# SchemaDriverMoteur.net
KiCad netlist of a schematic drawn in Altium Designer
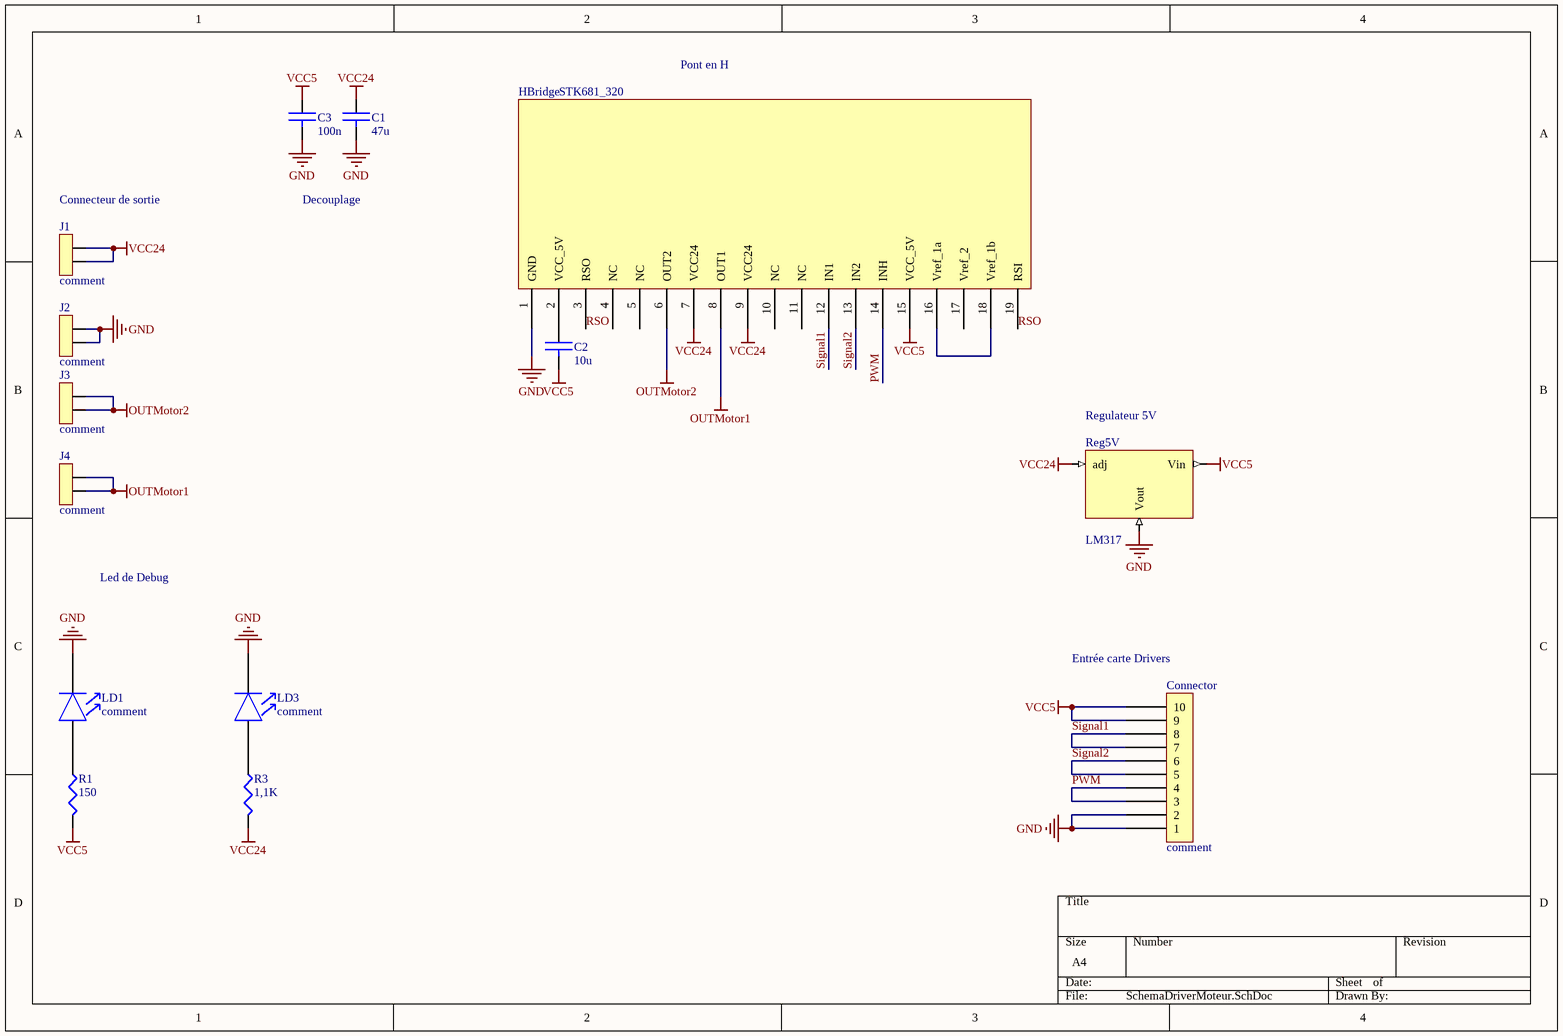
[diagram p0: SchemaDriverMoteur.SchDoc]

(export (version "E")
  (design (tool "Eeschema 10.0.6"))
  (components
    (comp (ref "C1")
      (value "47u")
      (footprint "RAD0.1")
      (description "capacité non polarisée")
      (fields (field (name "Comment") "CAP"))
      (libsource (lib "ISEN_basics") (part "CAP"))
    )
    (comp (ref "C2")
      (value "10u")
      (footprint "RAD0.1")
      (description "capacité non polarisée")
      (fields (field (name "Comment") "CAP"))
      (libsource (lib "ISEN_basics") (part "CAP"))
    )
    (comp (ref "C3")
      (value "100n")
      (footprint "0805")
      (description "capacité non polarisée")
      (fields (field (name "Comment") "CAP"))
      (libsource (lib "ISEN_basics") (part "CAP"))
    )
    (comp (ref "Connector")
      (value "comment")
      (footprint "HE10-10V")
      (description "10-pin connector")
      (libsource (lib "ISEN_basics") (part "HE10-10"))
    )
    (comp (ref "HBridge")
      (value "STK681_320")
      (footprint "stk681_320")
      (libsource (lib "STK681_320") (part "STK681_320"))
    )
    (comp (ref "J1")
      (value "comment")
      (footprint "AMP_2")
      (description "connecteur alim 2 pôles")
      (libsource (lib "ISEN_basics") (part "POWER2"))
    )
    (comp (ref "J2")
      (value "comment")
      (footprint "AMP_2")
      (description "connecteur alim 2 pôles")
      (libsource (lib "ISEN_basics") (part "POWER2"))
    )
    (comp (ref "J3")
      (value "comment")
      (footprint "AMP_2")
      (description "connecteur alim 2 pôles")
      (libsource (lib "ISEN_basics") (part "POWER2"))
    )
    (comp (ref "J4")
      (value "comment")
      (footprint "AMP_2")
      (description "connecteur alim 2 pôles")
      (libsource (lib "ISEN_basics") (part "POWER2"))
    )
    (comp (ref "LD1")
      (value "comment")
      (footprint "LED0805")
      (description "LED 5mm/3mm/CMS")
      (libsource (lib "ISEN_basics") (part "LED"))
    )
    (comp (ref "LD3")
      (value "comment")
      (footprint "LED0805")
      (description "LED 5mm/3mm/CMS")
      (libsource (lib "ISEN_basics") (part "LED"))
    )
    (comp (ref "R1")
      (value "150")
      (footprint "0805")
      (description "resistance")
      (fields (field (name "Comment") "RES"))
      (libsource (lib "ISEN_basics") (part "RES"))
    )
    (comp (ref "R3")
      (value "1,1K")
      (footprint "0805")
      (description "resistance")
      (fields (field (name "Comment") "RES"))
      (libsource (lib "ISEN_basics") (part "RES"))
    )
    (comp (ref "Reg5V")
      (value "LM317")
      (footprint "TO220V")
      (description "régulateur positif ajustable")
      (libsource (lib "ISEN_basics") (part "REG_ADJ_POS"))
    )
  )
  (nets
    (net (code "1") (name "/PWM") (class "Default")
      (node (ref "Connector") (pin "3") (pinfunction "3_3") (pintype "passive"))
      (node (ref "Connector") (pin "4") (pinfunction "4_4") (pintype "passive"))
      (node (ref "HBridge") (pin "14") (pinfunction "INH_14") (pintype "passive"))
    )
    (net (code "2") (name "/RSO") (class "Default")
      (node (ref "HBridge") (pin "19") (pinfunction "RSI_19") (pintype "passive"))
      (node (ref "HBridge") (pin "3") (pinfunction "RSO_3") (pintype "passive"))
    )
    (net (code "3") (name "/Signal1") (class "Default")
      (node (ref "Connector") (pin "7") (pinfunction "7_7") (pintype "passive"))
      (node (ref "Connector") (pin "8") (pinfunction "8_8") (pintype "passive"))
      (node (ref "HBridge") (pin "12") (pinfunction "IN1_12") (pintype "passive"))
    )
    (net (code "4") (name "/Signal2") (class "Default")
      (node (ref "Connector") (pin "5") (pinfunction "5_5") (pintype "passive"))
      (node (ref "Connector") (pin "6") (pinfunction "6_6") (pintype "passive"))
      (node (ref "HBridge") (pin "13") (pinfunction "IN2_13") (pintype "passive"))
    )
    (net (code "5") (name "GND") (class "Default")
      (node (ref "C1") (pin "2") (pinfunction "2_2") (pintype "passive"))
      (node (ref "C3") (pin "2") (pinfunction "2_2") (pintype "passive"))
      (node (ref "Connector") (pin "1") (pinfunction "1_1") (pintype "passive"))
      (node (ref "Connector") (pin "2") (pinfunction "2_2") (pintype "passive"))
      (node (ref "HBridge") (pin "1") (pinfunction "GND_1") (pintype "passive"))
      (node (ref "J2") (pin "1") (pintype "passive"))
      (node (ref "J2") (pin "2") (pintype "passive"))
      (node (ref "LD1") (pin "K") (pinfunction "10_K") (pintype "passive"))
      (node (ref "LD3") (pin "K") (pinfunction "10_K") (pintype "passive"))
      (node (ref "Reg5V") (pin "2") (pinfunction "Vout_2") (pintype "input"))
    )
    (net (code "6") (name "Net-(C2-Pad1)") (class "Default")
      (node (ref "C2") (pin "1") (pinfunction "1_1") (pintype "passive"))
      (node (ref "HBridge") (pin "2") (pinfunction "VCC_5V_2") (pintype "passive"))
    )
    (net (code "7") (name "Net-(HBridge-Vref_1a)") (class "Default")
      (node (ref "HBridge") (pin "16") (pinfunction "Vref_1a_16") (pintype "passive"))
      (node (ref "HBridge") (pin "18") (pinfunction "Vref_1b_18") (pintype "passive"))
    )
    (net (code "8") (name "Net-(LD1-8)") (class "Default")
      (node (ref "LD1") (pin "A") (pinfunction "8_A") (pintype "passive"))
      (node (ref "R1") (pin "1") (pintype "passive"))
    )
    (net (code "9") (name "Net-(LD3-8)") (class "Default")
      (node (ref "LD3") (pin "A") (pinfunction "8_A") (pintype "passive"))
      (node (ref "R3") (pin "1") (pintype "passive"))
    )
    (net (code "10") (name "OUTMotor1") (class "Default")
      (node (ref "HBridge") (pin "8") (pinfunction "OUT1_8") (pintype "passive"))
      (node (ref "J4") (pin "1") (pintype "passive"))
      (node (ref "J4") (pin "2") (pintype "passive"))
    )
    (net (code "11") (name "OUTMotor2") (class "Default")
      (node (ref "HBridge") (pin "6") (pinfunction "OUT2_6") (pintype "passive"))
      (node (ref "J3") (pin "1") (pintype "passive"))
      (node (ref "J3") (pin "2") (pintype "passive"))
    )
    (net (code "12") (name "VCC5") (class "Default")
      (node (ref "C2") (pin "2") (pinfunction "2_2") (pintype "passive"))
      (node (ref "C3") (pin "1") (pinfunction "1_1") (pintype "passive"))
      (node (ref "Connector") (pin "10") (pinfunction "10_10") (pintype "passive"))
      (node (ref "Connector") (pin "9") (pinfunction "9_9") (pintype "passive"))
      (node (ref "HBridge") (pin "15") (pinfunction "VCC_5V_15") (pintype "passive"))
      (node (ref "R1") (pin "2") (pintype "passive"))
      (node (ref "Reg5V") (pin "3") (pinfunction "Vin_3") (pintype "output"))
    )
    (net (code "13") (name "VCC24") (class "Default")
      (node (ref "C1") (pin "1") (pinfunction "1_1") (pintype "passive"))
      (node (ref "HBridge") (pin "7") (pinfunction "VCC24_7") (pintype "passive"))
      (node (ref "HBridge") (pin "9") (pinfunction "VCC24_9") (pintype "passive"))
      (node (ref "J1") (pin "1") (pintype "passive"))
      (node (ref "J1") (pin "2") (pintype "passive"))
      (node (ref "R3") (pin "2") (pintype "passive"))
      (node (ref "Reg5V") (pin "1") (pinfunction "adj_1") (pintype "input"))
    )
    (net (code "14") (name "unconnected-(HBridge-NC-Pad4)") (class "Default")
      (node (ref "HBridge") (pin "4") (pinfunction "NC_4") (pintype "passive"))
    )
    (net (code "15") (name "unconnected-(HBridge-NC-Pad5)") (class "Default")
      (node (ref "HBridge") (pin "5") (pinfunction "NC_5") (pintype "passive"))
    )
    (net (code "16") (name "unconnected-(HBridge-NC-Pad10)") (class "Default")
      (node (ref "HBridge") (pin "10") (pinfunction "NC_10") (pintype "passive"))
    )
    (net (code "17") (name "unconnected-(HBridge-NC-Pad11)") (class "Default")
      (node (ref "HBridge") (pin "11") (pinfunction "NC_11") (pintype "passive"))
    )
    (net (code "18") (name "unconnected-(HBridge-Vref_2-Pad17)") (class "Default")
      (node (ref "HBridge") (pin "17") (pinfunction "Vref_2_17") (pintype "passive"))
    )
  )
)
